# 36V_Supply.net
KiCad netlist of a schematic drawn in Altium Designer
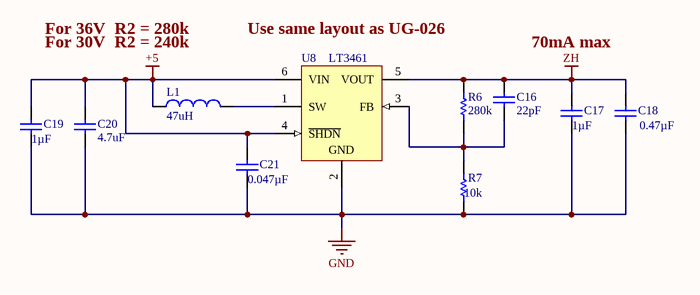
[diagram p0: 36V_Supply.SchDoc]

(export (version "E")
  (design (tool "Eeschema 10.0.6"))
  (components
    (comp (ref "C16")
      (value "22pF")
      (footprint "CAPC1206(3216)170_L")
      (description "CAP CER 22PF 50V C0G/NP0 1206")
      (fields
        (field (name "MANUFACTURER") "KEMET")
        (field (name "MANUFACTURER PART NUMBER") "C1206C220K5GACTU")
      )
      (libsource (lib "Altium Content Vault") (part "CMP-1037-04573-1"))
    )
    (comp (ref "C17")
      (value "CAP CER 1UF 50V X7R 1210")
      (footprint "CAPC1210(3225)100_N")
      (fields
        (field (name "MANUFACTURER") "Taiyo Yuden")
        (field (name "MANUFACTURER PART NUMBER") "UMK325B7105KH-T")
        (field (name "CAPACITANCE") "1µF")
        (field (name "TOLERANCE") "±10%")
      )
      (libsource (lib "Altium Content Vault") (part "CMP-1038-01123-1"))
    )
    (comp (ref "C18")
      (value "CAP CER 0.47UF 50V X7R 1206")
      (footprint "CAPC1206(3216)190_N")
      (fields
        (field (name "MANUFACTURER") "Taiyo Yuden")
        (field (name "MANUFACTURER PART NUMBER") "UMK316B7474KL-T")
        (field (name "CAPACITANCE") "0.47µF")
        (field (name "TOLERANCE") "±10%")
      )
      (libsource (lib "Altium Content Vault") (part "CMP-1037-04570-1"))
    )
    (comp (ref "C19")
      (value "CAP CER 1UF 16V X7R 0805")
      (footprint "CAPC0805(2012)145_N")
      (fields
        (field (name "MANUFACTURER") "Taiyo Yuden")
        (field (name "MANUFACTURER PART NUMBER") "EMK212B7105KG-T")
        (field (name "CAPACITANCE") "1µF")
        (field (name "TOLERANCE") "±10%")
      )
      (libsource (lib "Altium Content Vault") (part "CMP-1036-04795-1"))
    )
    (comp (ref "C20")
      (value "4.7uF")
      (footprint "CAPC0805(2012)145_M")
      (description "CAP CER 4.7UF 16V X7R 0805")
      (fields
        (field (name "MANUFACTURER") "KEMET")
        (field (name "MANUFACTURER PART NUMBER") "C0805C475K4RACTU")
      )
      (libsource (lib "Altium Content Vault") (part "CMP-1036-04750-1"))
    )
    (comp (ref "C21")
      (value "CAP CER 0.047UF 16V X7R 0603")
      (footprint "CAPC0805(2012)145_N")
      (fields
        (field (name "MANUFACTURER") "Murata Electronics North America")
        (field (name "MANUFACTURER PART NUMBER") "GRM188R71C473KA01D")
        (field (name "CAPACITANCE") "0.047µF")
        (field (name "TOLERANCE") "±10%")
      )
      (libsource (lib "Altium Content Vault") (part "CMP-1036-04795-1"))
    )
    (comp (ref "L1")
      (value "47uH")
      (footprint "C1210")
      (description "FIXED IND 47UH 170MA 1.3 OHM SMD")
      (fields
        (field (name "MANUFACTURER") "Murata Electronics North America")
        (field (name "MANUFACTURER PART NUMBER") "LQH32CN470K23L")
      )
      (libsource (lib "Miscellaneous Devices") (part "Inductor"))
    )
    (comp (ref "R6")
      (value "RES SMD 280K OHM 1% 1/8W 0805")
      (footprint "RESC0805(2012)_M")
      (fields
        (field (name "MANUFACTURER") "Vishay Dale")
        (field (name "MANUFACTURER PART NUMBER") "CRCW0805280KFKEA")
        (field (name "RESISTANCE (OHMS)") "280k")
        (field (name "TOLERANCE") "±1%")
      )
      (libsource (lib "Altium Content Vault") (part "CMP-1013-00017-1"))
    )
    (comp (ref "R7")
      (value "RES SMD 10K OHM 1% 1/8W 0805")
      (footprint "RESC0805(2012)_M")
      (fields
        (field (name "MANUFACTURER") "Yageo")
        (field (name "MANUFACTURER PART NUMBER") "RC0805FR-0710KL")
        (field (name "RESISTANCE (OHMS)") "10k")
        (field (name "TOLERANCE") "±1%")
      )
      (libsource (lib "Altium Content Vault") (part "CMP-1013-00017-1"))
    )
    (comp (ref "U8")
      (value "LT3461")
      (footprint "LT-S6-6-TSOT-23_N")
      (description "IC REG BOOST ADJ 0.3A TSOT23-6")
      (libsource (lib "Altium Content Vault") (part "CMP-0491-01698-1"))
    )
  )
  (nets
    (net (code "1") (name "+5") (class "Default")
      (node (ref "C19") (pin "2") (pinfunction "2_2") (pintype "passive"))
      (node (ref "C20") (pin "2") (pinfunction "2_2") (pintype "passive"))
      (node (ref "C21") (pin "2") (pinfunction "2_2") (pintype "passive"))
      (node (ref "L1") (pin "1") (pinfunction "1_1") (pintype "passive"))
      (node (ref "U8") (pin "4") (pinfunction "~{SHDN}_4") (pintype "input"))
      (node (ref "U8") (pin "6") (pinfunction "VIN_6") (pintype "power_in"))
    )
    (net (code "2") (name "GND") (class "Default")
      (node (ref "C17") (pin "1") (pinfunction "1_1") (pintype "passive"))
      (node (ref "C18") (pin "1") (pinfunction "1_1") (pintype "passive"))
      (node (ref "C19") (pin "1") (pinfunction "1_1") (pintype "passive"))
      (node (ref "C20") (pin "1") (pinfunction "1_1") (pintype "passive"))
      (node (ref "C21") (pin "1") (pinfunction "1_1") (pintype "passive"))
      (node (ref "R7") (pin "2") (pinfunction "2_2") (pintype "passive"))
      (node (ref "U8") (pin "2") (pinfunction "GND_2") (pintype "power_in"))
    )
    (net (code "3") (name "Net-(U8-FB)") (class "Default")
      (node (ref "C16") (pin "1") (pinfunction "1_1") (pintype "passive"))
      (node (ref "R6") (pin "2") (pinfunction "2_2") (pintype "passive"))
      (node (ref "R7") (pin "1") (pinfunction "1_1") (pintype "passive"))
      (node (ref "U8") (pin "3") (pinfunction "FB_3") (pintype "input"))
    )
    (net (code "4") (name "Net-(U8-SW)") (class "Default")
      (node (ref "L1") (pin "2") (pinfunction "2_2") (pintype "passive"))
      (node (ref "U8") (pin "1") (pinfunction "SW_1") (pintype "passive"))
    )
    (net (code "5") (name "ZH") (class "Default")
      (node (ref "C16") (pin "2") (pinfunction "2_2") (pintype "passive"))
      (node (ref "C17") (pin "2") (pinfunction "2_2") (pintype "passive"))
      (node (ref "C18") (pin "2") (pinfunction "2_2") (pintype "passive"))
      (node (ref "R6") (pin "1") (pinfunction "1_1") (pintype "passive"))
      (node (ref "U8") (pin "5") (pinfunction "VOUT_5") (pintype "power_in"))
    )
  )
)
